# tp1.net
KiCad netlist of a schematic drawn in Altium Designer
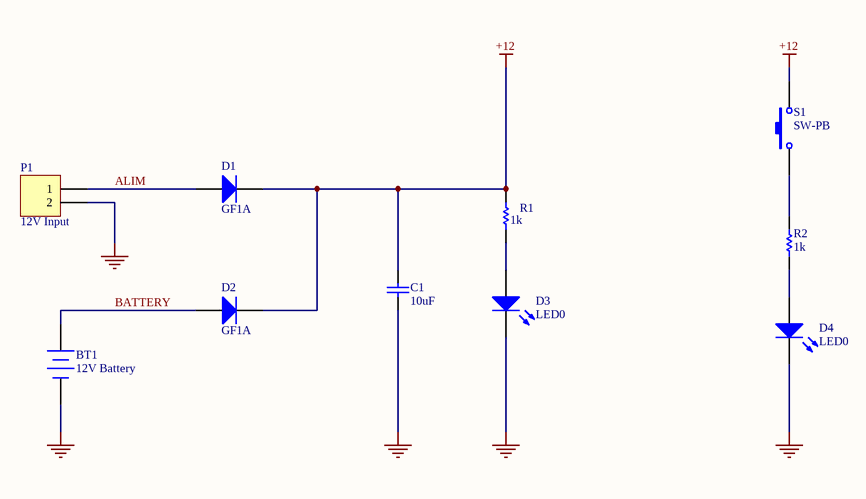
[diagram p0: tp1.SchDoc]

(export (version "E")
  (design (tool "Eeschema 10.0.6"))
  (components
    (comp (ref "BT1")
      (value "12V Battery")
      (footprint "BAT-2")
      (description "Multicell Battery")
      (fields (field (name "PUBLISHER") "Altium Limited"))
      (libsource (lib "Miscellaneous Devices") (part "Battery"))
    )
    (comp (ref "C1")
      (value "10uF")
      (footprint "RAD-0.3")
      (description "Capacitor")
      (fields (field (name "PUBLISHER") "Altium Limited"))
      (libsource (lib "Miscellaneous Devices") (part "Cap"))
    )
    (comp (ref "D1")
      (value "GF1A")
      (footprint "SMC")
      (description "Default Diode")
      (fields (field (name "PUBLISHER") "Altium Limited"))
      (libsource (lib "Miscellaneous Devices") (part "Diode"))
    )
    (comp (ref "D2")
      (value "GF1A")
      (footprint "SMC")
      (description "Default Diode")
      (fields (field (name "PUBLISHER") "Altium Limited"))
      (libsource (lib "Miscellaneous Devices") (part "Diode"))
    )
    (comp (ref "D3")
      (value "LED0")
      (footprint "LED-0")
      (description "Typical INFRARED GaAs LED")
      (fields (field (name "PUBLISHER") "Altium Limited"))
      (libsource (lib "Miscellaneous Devices") (part "LED0"))
    )
    (comp (ref "D4")
      (value "LED0")
      (footprint "LED-0")
      (description "Typical INFRARED GaAs LED")
      (fields (field (name "PUBLISHER") "Altium Limited"))
      (libsource (lib "Miscellaneous Devices") (part "LED0"))
    )
    (comp (ref "P1")
      (value "12V Input")
      (footprint "MHDR1X2")
      (description "Header, 2-Pin")
      (fields (field (name "PUBLISHER") "Altium Limited"))
      (libsource (lib "Miscellaneous Connectors") (part "MHDR1X2"))
    )
    (comp (ref "R1")
      (value "1k")
      (footprint "AXIAL-0.3")
      (description "Resistor")
      (fields (field (name "PUBLISHER") "Altium Limited"))
      (libsource (lib "Miscellaneous Devices") (part "Res1"))
    )
    (comp (ref "R2")
      (value "1k")
      (footprint "AXIAL-0.3")
      (description "Resistor")
      (fields (field (name "PUBLISHER") "Altium Limited"))
      (libsource (lib "Miscellaneous Devices") (part "Res1"))
    )
    (comp (ref "S1")
      (value "SW-PB")
      (footprint "SPST-2")
      (description "Switch")
      (fields (field (name "PUBLISHER") "Altium Limited"))
      (libsource (lib "Miscellaneous Devices") (part "SW-PB"))
    )
  )
  (nets
    (net (code "1") (name "+12") (class "Default")
      (node (ref "C1") (pin "2") (pinfunction "2_2") (pintype "passive"))
      (node (ref "D1") (pin "2") (pinfunction "K_2") (pintype "passive"))
      (node (ref "D2") (pin "2") (pinfunction "K_2") (pintype "passive"))
      (node (ref "R1") (pin "2") (pinfunction "2_2") (pintype "passive"))
      (node (ref "S1") (pin "2") (pinfunction "2_2") (pintype "passive"))
    )
    (net (code "2") (name "/ALIM") (class "Default")
      (node (ref "D1") (pin "1") (pinfunction "A_1") (pintype "passive"))
      (node (ref "P1") (pin "1") (pinfunction "1_1") (pintype "passive"))
    )
    (net (code "3") (name "/BATTERY") (class "Default")
      (node (ref "BT1") (pin "1") (pinfunction "+_1") (pintype "passive"))
      (node (ref "D2") (pin "1") (pinfunction "A_1") (pintype "passive"))
    )
    (net (code "4") (name "GND") (class "Default")
      (node (ref "BT1") (pin "2") (pinfunction "-_2") (pintype "passive"))
      (node (ref "C1") (pin "1") (pinfunction "1_1") (pintype "passive"))
      (node (ref "D3") (pin "2") (pinfunction "K_2") (pintype "passive"))
      (node (ref "D4") (pin "2") (pinfunction "K_2") (pintype "passive"))
      (node (ref "P1") (pin "2") (pinfunction "2_2") (pintype "passive"))
    )
    (net (code "5") (name "Net-(D3-A)") (class "Default")
      (node (ref "D3") (pin "1") (pinfunction "A_1") (pintype "passive"))
      (node (ref "R1") (pin "1") (pinfunction "1_1") (pintype "passive"))
    )
    (net (code "6") (name "Net-(D4-A)") (class "Default")
      (node (ref "D4") (pin "1") (pinfunction "A_1") (pintype "passive"))
      (node (ref "R2") (pin "1") (pinfunction "1_1") (pintype "passive"))
    )
    (net (code "7") (name "Net-(R2-Pad2)") (class "Default")
      (node (ref "R2") (pin "2") (pinfunction "2_2") (pintype "passive"))
      (node (ref "S1") (pin "1") (pinfunction "1_1") (pintype "passive"))
    )
  )
)
